# page1.net
KiCad netlist of a schematic drawn in EAGLE
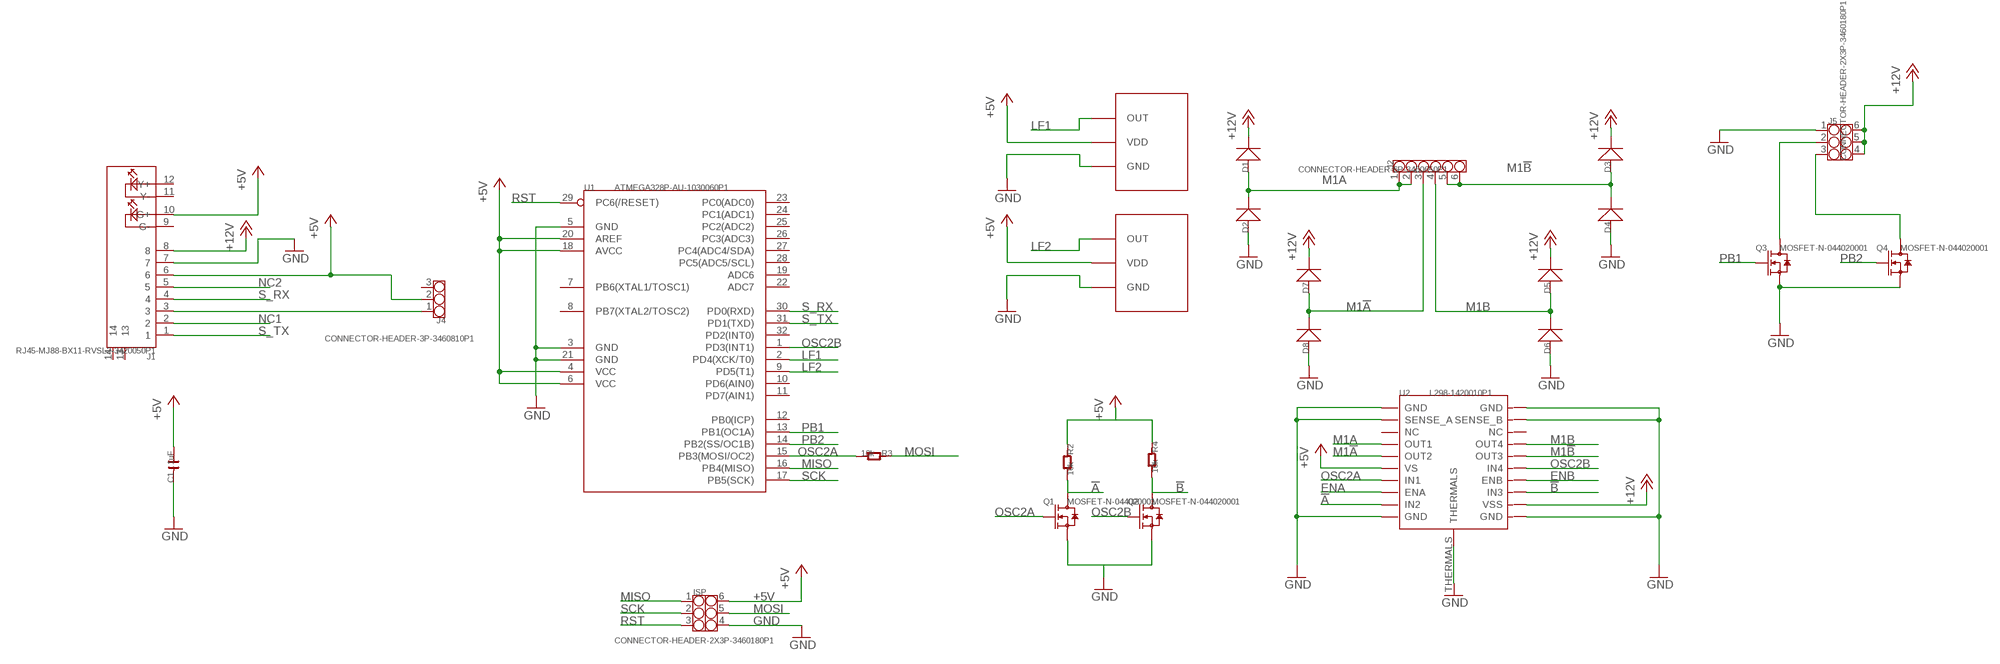
[diagram p0: schematic, sheet 1]

(export (version "E")
  (design (tool "Eeschema 10.0.6"))
  (components
    (comp (ref "C1")
      (value "1uF")
      (footprint "eagle-import:C0805")
      (libsource (lib "eagle-import") (part "C-0805"))
    )
    (comp (ref "D1")
      (value "D-SMA")
      (footprint "eagle-import:DO-214AC")
      (libsource (lib "eagle-import") (part "D-SMA"))
    )
    (comp (ref "D2")
      (value "D-SMA")
      (footprint "eagle-import:DO-214AC")
      (libsource (lib "eagle-import") (part "D-SMA"))
    )
    (comp (ref "D3")
      (value "D-SMA")
      (footprint "eagle-import:DO-214AC")
      (libsource (lib "eagle-import") (part "D-SMA"))
    )
    (comp (ref "D4")
      (value "D-SMA")
      (footprint "eagle-import:DO-214AC")
      (libsource (lib "eagle-import") (part "D-SMA"))
    )
    (comp (ref "D5")
      (value "D-SMA")
      (footprint "eagle-import:DO-214AC")
      (libsource (lib "eagle-import") (part "D-SMA"))
    )
    (comp (ref "D6")
      (value "D-SMA")
      (footprint "eagle-import:DO-214AC")
      (libsource (lib "eagle-import") (part "D-SMA"))
    )
    (comp (ref "D7")
      (value "D-SMA")
      (footprint "eagle-import:DO-214AC")
      (libsource (lib "eagle-import") (part "D-SMA"))
    )
    (comp (ref "D8")
      (value "D-SMA")
      (footprint "eagle-import:DO-214AC")
      (libsource (lib "eagle-import") (part "D-SMA"))
    )
    (comp (ref "ISP")
      (value "CONNECTOR-HEADER-2X3P-3460180P1")
      (footprint "eagle-import:2X3P-2.54-2.54-11.6-3.0-BLACK-MALE")
      (libsource (lib "eagle-import") (part "CONNECTOR-HEADER-2X3P-3460180P1"))
    )
    (comp (ref "J1")
      (value "RJ45-MJ88-BX11-RVSL2-3420050P1")
      (footprint "eagle-import:RJ45-MJ88-BX11-RVSL2")
      (libsource (lib "eagle-import") (part "RJ45-MJ88-BX11-RVSL2-3420050P1"))
    )
    (comp (ref "J2")
      (value "CONNECTOR-HEADER-6P-3460650P1")
      (footprint "eagle-import:1X6P-2.54-2.54-11.6-3.0-BLACK-MALE")
      (libsource (lib "eagle-import") (part "CONNECTOR-HEADER-6P-3460650P1"))
    )
    (comp (ref "J4")
      (value "CONNECTOR-HEADER-3P-3460810P1")
      (footprint "eagle-import:1X3P-2.54-2.54-11.6-3.0-BLACK-MALE")
      (libsource (lib "eagle-import") (part "CONNECTOR-HEADER-3P-3460810P1"))
    )
    (comp (ref "J5")
      (value "CONNECTOR-HEADER-2X3P-3460180P1")
      (footprint "eagle-import:2X3P-2.54-2.54-11.6-3.0-BLACK-MALE")
      (libsource (lib "eagle-import") (part "CONNECTOR-HEADER-2X3P-3460180P1"))
    )
    (comp (ref "Q1")
      (value "MOSFET-N-044020001")
      (footprint "eagle-import:SOT23")
      (libsource (lib "eagle-import") (part "MOSFET-N-044020001"))
    )
    (comp (ref "Q2")
      (value "MOSFET-N-044020001")
      (footprint "eagle-import:SOT23")
      (libsource (lib "eagle-import") (part "MOSFET-N-044020001"))
    )
    (comp (ref "Q3")
      (value "MOSFET-N-044020001")
      (footprint "eagle-import:SOT23")
      (libsource (lib "eagle-import") (part "MOSFET-N-044020001"))
    )
    (comp (ref "Q4")
      (value "MOSFET-N-044020001")
      (footprint "eagle-import:SOT23")
      (libsource (lib "eagle-import") (part "MOSFET-N-044020001"))
    )
    (comp (ref "R2")
      (value "10k")
      (footprint "eagle-import:R0603")
      (libsource (lib "eagle-import") (part "R-0603"))
    )
    (comp (ref "R3")
      (value "10k")
      (footprint "eagle-import:R0603")
      (libsource (lib "eagle-import") (part "R-0603"))
    )
    (comp (ref "R4")
      (value "10k")
      (footprint "eagle-import:R0603")
      (libsource (lib "eagle-import") (part "R-0603"))
    )
    (comp (ref "U$5")
      (value "TSL235")
      (footprint "eagle-import:TSL235R-2MM-S")
      (libsource (lib "eagle-import") (part "TSL235"))
    )
    (comp (ref "U$6")
      (value "TSL235")
      (footprint "eagle-import:TSL235R-2MM-S")
      (libsource (lib "eagle-import") (part "TSL235"))
    )
    (comp (ref "U1")
      (value "ATMEGA328P-AU-1030060P1")
      (footprint "eagle-import:TQFP32")
      (libsource (lib "eagle-import") (part "ATMEGA328P-AU-1030060P1"))
    )
    (comp (ref "U2")
      (value "L298-1420010P1")
      (footprint "eagle-import:POWERSO-20")
      (libsource (lib "eagle-import") (part "L298-1420010P1"))
    )
  )
  (nets
    (net (code "1") (name "+5V") (class "Default")
      (node (ref "C1") (pin "2") (pinfunction "2_2") (pintype "bidirectional"))
      (node (ref "ISP") (pin "6") (pinfunction "6_6") (pintype "bidirectional"))
      (node (ref "J1") (pin "10") (pinfunction "G+_10") (pintype "bidirectional"))
      (node (ref "J1") (pin "6") (pinfunction "6_6") (pintype "bidirectional"))
      (node (ref "J4") (pin "2") (pinfunction "2_2") (pintype "bidirectional"))
      (node (ref "R2") (pin "1") (pinfunction "1_1") (pintype "bidirectional"))
      (node (ref "R4") (pin "1") (pinfunction "1_1") (pintype "bidirectional"))
      (node (ref "U$5") (pin "P$2") (pinfunction "VDD_P$2") (pintype "bidirectional"))
      (node (ref "U$6") (pin "P$2") (pinfunction "VDD_P$2") (pintype "bidirectional"))
      (node (ref "U1") (pin "18") (pinfunction "AVCC_18") (pintype "bidirectional"))
      (node (ref "U1") (pin "20") (pinfunction "AREF_20") (pintype "bidirectional"))
      (node (ref "U1") (pin "4") (pinfunction "VCC_4") (pintype "bidirectional"))
      (node (ref "U1") (pin "6") (pinfunction "VCC_6") (pintype "bidirectional"))
      (node (ref "U2") (pin "6") (pinfunction "VS_6") (pintype "bidirectional"))
    )
    (net (code "2") (name "+12V") (class "Default")
      (node (ref "D1") (pin "2") (pinfunction "-_2") (pintype "passive"))
      (node (ref "D3") (pin "2") (pinfunction "-_2") (pintype "passive"))
      (node (ref "D5") (pin "2") (pinfunction "-_2") (pintype "passive"))
      (node (ref "D7") (pin "2") (pinfunction "-_2") (pintype "passive"))
      (node (ref "J1") (pin "8") (pinfunction "8_8") (pintype "bidirectional"))
      (node (ref "J5") (pin "4") (pinfunction "4_4") (pintype "bidirectional"))
      (node (ref "J5") (pin "5") (pinfunction "5_5") (pintype "bidirectional"))
      (node (ref "J5") (pin "6") (pinfunction "6_6") (pintype "bidirectional"))
      (node (ref "U2") (pin "12") (pinfunction "VSS_12") (pintype "bidirectional"))
    )
    (net (code "3") (name "/ENA") (class "Default")
      (node (ref "U2") (pin "8") (pinfunction "ENA_8") (pintype "bidirectional"))
    )
    (net (code "4") (name "/ENB") (class "Default")
      (node (ref "U2") (pin "14") (pinfunction "ENB_14") (pintype "bidirectional"))
    )
    (net (code "5") (name "/LF1") (class "Default")
      (node (ref "U$5") (pin "P$3") (pinfunction "OUT_P$3") (pintype "output"))
      (node (ref "U1") (pin "2") (pinfunction "PD4(XCK/T0)_2") (pintype "bidirectional"))
    )
    (net (code "6") (name "/LF2") (class "Default")
      (node (ref "U$6") (pin "P$3") (pinfunction "OUT_P$3") (pintype "output"))
      (node (ref "U1") (pin "9") (pinfunction "PD5(T1)_9") (pintype "bidirectional"))
    )
    (net (code "7") (name "/M1A") (class "Default")
      (node (ref "D1") (pin "1") (pinfunction "+_1") (pintype "passive"))
      (node (ref "D2") (pin "2") (pinfunction "-_2") (pintype "passive"))
      (node (ref "J2") (pin "1") (pinfunction "1_1") (pintype "bidirectional"))
      (node (ref "J2") (pin "2") (pinfunction "2_2") (pintype "bidirectional"))
      (node (ref "U2") (pin "4") (pinfunction "OUT1_4") (pintype "bidirectional"))
    )
    (net (code "8") (name "/M1B") (class "Default")
      (node (ref "D5") (pin "1") (pinfunction "+_1") (pintype "passive"))
      (node (ref "D6") (pin "2") (pinfunction "-_2") (pintype "passive"))
      (node (ref "J2") (pin "4") (pinfunction "4_4") (pintype "bidirectional"))
      (node (ref "U2") (pin "17") (pinfunction "OUT4_17") (pintype "bidirectional"))
    )
    (net (code "9") (name "/M1~{A}") (class "Default")
      (node (ref "D7") (pin "1") (pinfunction "+_1") (pintype "passive"))
      (node (ref "D8") (pin "2") (pinfunction "-_2") (pintype "passive"))
      (node (ref "J2") (pin "3") (pinfunction "3_3") (pintype "bidirectional"))
      (node (ref "U2") (pin "5") (pinfunction "OUT2_5") (pintype "bidirectional"))
    )
    (net (code "10") (name "/M1~{B}") (class "Default")
      (node (ref "D3") (pin "1") (pinfunction "+_1") (pintype "passive"))
      (node (ref "D4") (pin "2") (pinfunction "-_2") (pintype "passive"))
      (node (ref "J2") (pin "5") (pinfunction "5_5") (pintype "bidirectional"))
      (node (ref "J2") (pin "6") (pinfunction "6_6") (pintype "bidirectional"))
      (node (ref "U2") (pin "16") (pinfunction "OUT3_16") (pintype "bidirectional"))
    )
    (net (code "11") (name "/MISO") (class "Default")
      (node (ref "ISP") (pin "1") (pinfunction "1_1") (pintype "bidirectional"))
      (node (ref "U1") (pin "16") (pinfunction "PB4(MISO)_16") (pintype "bidirectional"))
    )
    (net (code "12") (name "/MOSI") (class "Default")
      (node (ref "ISP") (pin "5") (pinfunction "5_5") (pintype "bidirectional"))
      (node (ref "R3") (pin "1") (pinfunction "1_1") (pintype "bidirectional"))
    )
    (net (code "13") (name "/NC1") (class "Default")
      (node (ref "J1") (pin "2") (pinfunction "2_2") (pintype "bidirectional"))
    )
    (net (code "14") (name "/NC2") (class "Default")
      (node (ref "J1") (pin "5") (pinfunction "5_5") (pintype "bidirectional"))
    )
    (net (code "15") (name "/OSC2A") (class "Default")
      (node (ref "Q1") (pin "1") (pinfunction "G_1") (pintype "passive"))
      (node (ref "R3") (pin "2") (pinfunction "2_2") (pintype "bidirectional"))
      (node (ref "U1") (pin "15") (pinfunction "PB3(MOSI/OC2)_15") (pintype "bidirectional"))
      (node (ref "U2") (pin "7") (pinfunction "IN1_7") (pintype "bidirectional"))
    )
    (net (code "16") (name "/OSC2B") (class "Default")
      (node (ref "Q2") (pin "1") (pinfunction "G_1") (pintype "passive"))
      (node (ref "U1") (pin "1") (pinfunction "PD3(INT1)_1") (pintype "bidirectional"))
      (node (ref "U2") (pin "15") (pinfunction "IN4_15") (pintype "bidirectional"))
    )
    (net (code "17") (name "/PB1") (class "Default")
      (node (ref "Q3") (pin "1") (pinfunction "G_1") (pintype "passive"))
      (node (ref "U1") (pin "13") (pinfunction "PB1(OC1A)_13") (pintype "bidirectional"))
    )
    (net (code "18") (name "/PB2") (class "Default")
      (node (ref "Q4") (pin "1") (pinfunction "G_1") (pintype "passive"))
      (node (ref "U1") (pin "14") (pinfunction "PB2(SS/OC1B)_14") (pintype "bidirectional"))
    )
    (net (code "19") (name "/RST") (class "Default")
      (node (ref "ISP") (pin "3") (pinfunction "3_3") (pintype "bidirectional"))
      (node (ref "U1") (pin "29") (pinfunction "PC6(/RESET)_29") (pintype "bidirectional"))
    )
    (net (code "20") (name "/SCK") (class "Default")
      (node (ref "ISP") (pin "2") (pinfunction "2_2") (pintype "bidirectional"))
      (node (ref "U1") (pin "17") (pinfunction "PB5(SCK)_17") (pintype "bidirectional"))
    )
    (net (code "21") (name "/S_RX") (class "Default")
      (node (ref "J1") (pin "4") (pinfunction "4_4") (pintype "bidirectional"))
      (node (ref "U1") (pin "30") (pinfunction "PD0(RXD)_30") (pintype "bidirectional"))
    )
    (net (code "22") (name "/S_TX") (class "Default")
      (node (ref "J1") (pin "1") (pinfunction "1_1") (pintype "bidirectional"))
      (node (ref "U1") (pin "31") (pinfunction "PD1(TXD)_31") (pintype "bidirectional"))
    )
    (net (code "23") (name "/~{A}") (class "Default")
      (node (ref "Q1") (pin "3") (pinfunction "D_3") (pintype "passive"))
      (node (ref "R2") (pin "2") (pinfunction "2_2") (pintype "bidirectional"))
      (node (ref "U2") (pin "9") (pinfunction "IN2_9") (pintype "bidirectional"))
    )
    (net (code "24") (name "/~{B}") (class "Default")
      (node (ref "Q2") (pin "3") (pinfunction "D_3") (pintype "passive"))
      (node (ref "R4") (pin "2") (pinfunction "2_2") (pintype "bidirectional"))
      (node (ref "U2") (pin "13") (pinfunction "IN3_13") (pintype "bidirectional"))
    )
    (net (code "25") (name "GND") (class "Default")
      (node (ref "C1") (pin "1") (pinfunction "1_1") (pintype "bidirectional"))
      (node (ref "D2") (pin "1") (pinfunction "+_1") (pintype "passive"))
      (node (ref "D4") (pin "1") (pinfunction "+_1") (pintype "passive"))
      (node (ref "D6") (pin "1") (pinfunction "+_1") (pintype "passive"))
      (node (ref "D8") (pin "1") (pinfunction "+_1") (pintype "passive"))
      (node (ref "ISP") (pin "4") (pinfunction "4_4") (pintype "bidirectional"))
      (node (ref "J1") (pin "7") (pinfunction "7_7") (pintype "bidirectional"))
      (node (ref "J5") (pin "1") (pinfunction "1_1") (pintype "bidirectional"))
      (node (ref "Q1") (pin "2") (pinfunction "S_2") (pintype "passive"))
      (node (ref "Q2") (pin "2") (pinfunction "S_2") (pintype "passive"))
      (node (ref "Q3") (pin "2") (pinfunction "S_2") (pintype "passive"))
      (node (ref "Q4") (pin "2") (pinfunction "S_2") (pintype "passive"))
      (node (ref "U$5") (pin "P$1") (pinfunction "GND_P$1") (pintype "bidirectional"))
      (node (ref "U$6") (pin "P$1") (pinfunction "GND_P$1") (pintype "bidirectional"))
      (node (ref "U1") (pin "21") (pinfunction "GND_21") (pintype "bidirectional"))
      (node (ref "U1") (pin "3") (pinfunction "GND_3") (pintype "bidirectional"))
      (node (ref "U1") (pin "5") (pinfunction "GND_5") (pintype "bidirectional"))
      (node (ref "U2") (pin "1") (pinfunction "GND_1") (pintype "bidirectional"))
      (node (ref "U2") (pin "10") (pinfunction "GND_10") (pintype "bidirectional"))
      (node (ref "U2") (pin "11") (pinfunction "GND_11") (pintype "bidirectional"))
      (node (ref "U2") (pin "19") (pinfunction "SENSE_B_19") (pintype "bidirectional"))
      (node (ref "U2") (pin "2") (pinfunction "SENSE_A_2") (pintype "bidirectional"))
      (node (ref "U2") (pin "20") (pinfunction "GND_20") (pintype "bidirectional"))
      (node (ref "U2") (pin "THERMALS") (pinfunction "THERMALS_THERMALS") (pintype "bidirectional"))
    )
    (net (code "26") (name "Net-(J1-Pad3)") (class "Default")
      (node (ref "J1") (pin "3") (pinfunction "3_3") (pintype "bidirectional"))
      (node (ref "J4") (pin "1") (pinfunction "1_1") (pintype "bidirectional"))
    )
    (net (code "27") (name "Net-(Q3-D)") (class "Default")
      (node (ref "J5") (pin "2") (pinfunction "2_2") (pintype "bidirectional"))
      (node (ref "Q3") (pin "3") (pinfunction "D_3") (pintype "passive"))
    )
    (net (code "28") (name "Net-(Q4-D)") (class "Default")
      (node (ref "J5") (pin "3") (pinfunction "3_3") (pintype "bidirectional"))
      (node (ref "Q4") (pin "3") (pinfunction "D_3") (pintype "passive"))
    )
    (net (code "29") (name "unconnected-(J1-G--Pad9)") (class "Default")
      (node (ref "J1") (pin "9") (pinfunction "G-_9") (pintype "bidirectional"))
    )
    (net (code "30") (name "unconnected-(J1-Pad13)") (class "Default")
      (node (ref "J1") (pin "13") (pinfunction "13_13") (pintype "bidirectional"))
    )
    (net (code "31") (name "unconnected-(J1-Pad14)") (class "Default")
      (node (ref "J1") (pin "14") (pinfunction "14_14") (pintype "bidirectional"))
    )
    (net (code "32") (name "unconnected-(J1-Y+-Pad12)") (class "Default")
      (node (ref "J1") (pin "12") (pinfunction "Y+_12") (pintype "bidirectional"))
    )
    (net (code "33") (name "unconnected-(J1-Y--Pad11)") (class "Default")
      (node (ref "J1") (pin "11") (pinfunction "Y-_11") (pintype "bidirectional"))
    )
    (net (code "34") (name "unconnected-(J4-Pad3)") (class "Default")
      (node (ref "J4") (pin "3") (pinfunction "3_3") (pintype "bidirectional"))
    )
    (net (code "35") (name "unconnected-(U1-ADC6-Pad19)") (class "Default")
      (node (ref "U1") (pin "19") (pinfunction "ADC6_19") (pintype "bidirectional"))
    )
    (net (code "36") (name "unconnected-(U1-ADC7-Pad22)") (class "Default")
      (node (ref "U1") (pin "22") (pinfunction "ADC7_22") (pintype "bidirectional"))
    )
    (net (code "37") (name "unconnected-(U1-PB0(ICP)-Pad12)") (class "Default")
      (node (ref "U1") (pin "12") (pinfunction "PB0(ICP)_12") (pintype "bidirectional"))
    )
    (net (code "38") (name "unconnected-(U1-PB6(XTAL1{slash}TOSC1)-Pad7)") (class "Default")
      (node (ref "U1") (pin "7") (pinfunction "PB6(XTAL1/TOSC1)_7") (pintype "bidirectional"))
    )
    (net (code "39") (name "unconnected-(U1-PB7(XTAL2{slash}TOSC2)-Pad8)") (class "Default")
      (node (ref "U1") (pin "8") (pinfunction "PB7(XTAL2/TOSC2)_8") (pintype "bidirectional"))
    )
    (net (code "40") (name "unconnected-(U1-PC0(ADC0)-Pad23)") (class "Default")
      (node (ref "U1") (pin "23") (pinfunction "PC0(ADC0)_23") (pintype "bidirectional"))
    )
    (net (code "41") (name "unconnected-(U1-PC1(ADC1)-Pad24)") (class "Default")
      (node (ref "U1") (pin "24") (pinfunction "PC1(ADC1)_24") (pintype "bidirectional"))
    )
    (net (code "42") (name "unconnected-(U1-PC2(ADC2)-Pad25)") (class "Default")
      (node (ref "U1") (pin "25") (pinfunction "PC2(ADC2)_25") (pintype "bidirectional"))
    )
    (net (code "43") (name "unconnected-(U1-PC3(ADC3)-Pad26)") (class "Default")
      (node (ref "U1") (pin "26") (pinfunction "PC3(ADC3)_26") (pintype "bidirectional"))
    )
    (net (code "44") (name "unconnected-(U1-PC4(ADC4{slash}SDA)-Pad27)") (class "Default")
      (node (ref "U1") (pin "27") (pinfunction "PC4(ADC4/SDA)_27") (pintype "bidirectional"))
    )
    (net (code "45") (name "unconnected-(U1-PC5(ADC5{slash}SCL)-Pad28)") (class "Default")
      (node (ref "U1") (pin "28") (pinfunction "PC5(ADC5/SCL)_28") (pintype "bidirectional"))
    )
    (net (code "46") (name "unconnected-(U1-PD2(INT0)-Pad32)") (class "Default")
      (node (ref "U1") (pin "32") (pinfunction "PD2(INT0)_32") (pintype "bidirectional"))
    )
    (net (code "47") (name "unconnected-(U1-PD6(AIN0)-Pad10)") (class "Default")
      (node (ref "U1") (pin "10") (pinfunction "PD6(AIN0)_10") (pintype "bidirectional"))
    )
    (net (code "48") (name "unconnected-(U1-PD7(AIN1)-Pad11)") (class "Default")
      (node (ref "U1") (pin "11") (pinfunction "PD7(AIN1)_11") (pintype "bidirectional"))
    )
    (net (code "49") (name "unconnected-(U2-NC-Pad3)") (class "Default")
      (node (ref "U2") (pin "3") (pinfunction "NC_3") (pintype "bidirectional"))
    )
    (net (code "50") (name "unconnected-(U2-NC-Pad18)") (class "Default")
      (node (ref "U2") (pin "18") (pinfunction "NC_18") (pintype "bidirectional"))
    )
  )
)
